# operator_mk2.net
KiCad netlist of a schematic drawn in EAGLE
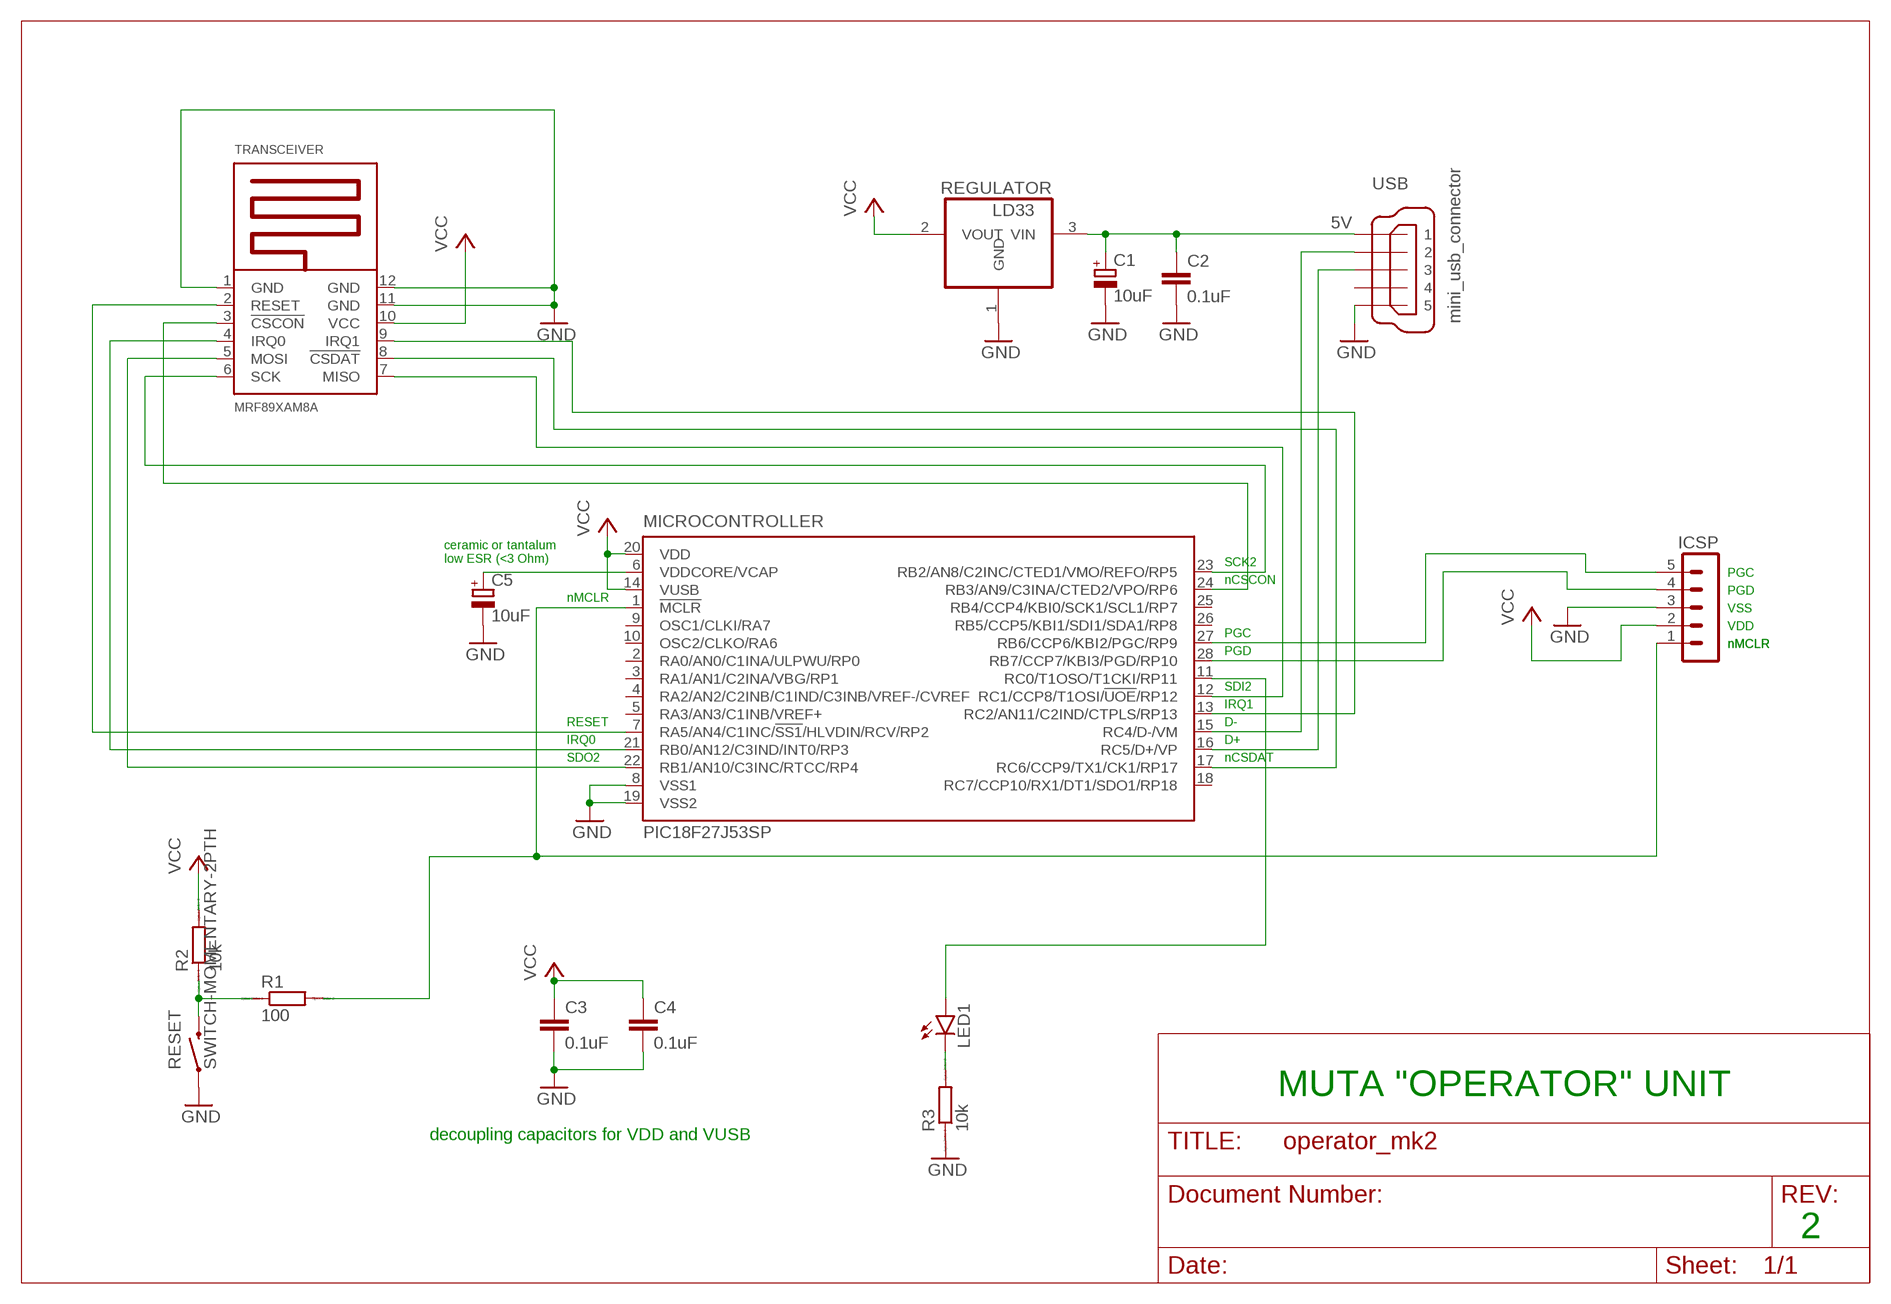
[diagram p0: schematic, sheet 1]

(export (version "E")
  (design (tool "Eeschema 10.0.6"))
  (components
    (comp (ref "C1")
      (value "10uF")
      (footprint "eagle-import:TT5D6")
      (libsource (lib "eagle-import") (part "CPOL-EUTT6D6"))
    )
    (comp (ref "C2")
      (value "0.1uF")
      (footprint "eagle-import:C050-025X075")
      (libsource (lib "eagle-import") (part "C-EU050-025X075"))
    )
    (comp (ref "C3")
      (value "0.1uF")
      (footprint "eagle-import:C050-025X075")
      (libsource (lib "eagle-import") (part "C-EU050-025X075"))
    )
    (comp (ref "C4")
      (value "0.1uF")
      (footprint "eagle-import:C050-025X075")
      (libsource (lib "eagle-import") (part "C-EU050-025X075"))
    )
    (comp (ref "C5")
      (value "10uF")
      (footprint "eagle-import:C_6032-28R")
      (libsource (lib "eagle-import") (part "CPOL-EUC/6032-28R"))
    )
    (comp (ref "ICSP")
      (value "MA05-1")
      (footprint "eagle-import:MA05-1")
      (libsource (lib "eagle-import") (part "MA05-1"))
    )
    (comp (ref "LED1")
      (value "LED5MM")
      (footprint "eagle-import:LED5MM")
      (libsource (lib "eagle-import") (part "LED5MM"))
    )
    (comp (ref "MICROCONTROLLER")
      (value "PIC18F27J53SP")
      (footprint "eagle-import:DIL28-3")
      (fields (field (name "MPN") "PIC18F27J53-I/SP"))
      (libsource (lib "eagle-import") (part "PIC18F2J53SP7"))
    )
    (comp (ref "R1")
      (value "100")
      (footprint "eagle-import:0207_10")
      (libsource (lib "eagle-import") (part "R-EU_0207_10"))
    )
    (comp (ref "R2")
      (value "10k")
      (footprint "eagle-import:0207_10")
      (libsource (lib "eagle-import") (part "R-EU_0207_10"))
    )
    (comp (ref "R3")
      (value "10k")
      (footprint "eagle-import:0207_2V")
      (libsource (lib "eagle-import") (part "R-EU_0207_2V"))
    )
    (comp (ref "REGULATOR")
      (value "LD33")
      (footprint "eagle-import:SOT223")
      (fields (field (name "MPN") "REG1117") (field (name "MPN_1") "LD33"))
      (libsource (lib "eagle-import") (part "REG1117"))
    )
    (comp (ref "RESET")
      (value "SWITCH-MOMENTARY-2PTH")
      (footprint "eagle-import:TACTILE-PTH")
      (libsource (lib "eagle-import") (part "SWITCH-MOMENTARY-2PTH"))
    )
    (comp (ref "TRANSCEIVER")
      (value "MRF89XAM8A")
      (footprint "eagle-import:MRF89XAMXA")
      (libsource (lib "eagle-import") (part "MRF89XAM8A"))
    )
    (comp (ref "USB")
      (value "mini_usb_connector")
      (footprint "eagle-import:UX60-MB-5ST")
      (libsource (lib "eagle-import") (part "MINI-USB-UX60-MB-5ST"))
    )
  )
  (nets
    (net (code "1") (name "/5V") (class "Default")
      (node (ref "C1") (pin "+") (pinfunction "+_+") (pintype "passive"))
      (node (ref "C2") (pin "1") (pinfunction "1_1") (pintype "passive"))
      (node (ref "REGULATOR") (pin "3") (pinfunction "VIN_3") (pintype "input"))
      (node (ref "USB") (pin "1") (pinfunction "1_1") (pintype "input"))
    )
    (net (code "2") (name "GND") (class "Default")
      (node (ref "C1") (pin "-") (pinfunction "-_-") (pintype "passive"))
      (node (ref "C2") (pin "2") (pinfunction "2_2") (pintype "passive"))
      (node (ref "C3") (pin "2") (pinfunction "2_2") (pintype "passive"))
      (node (ref "C4") (pin "2") (pinfunction "2_2") (pintype "passive"))
      (node (ref "C5") (pin "-") (pinfunction "-_-") (pintype "passive"))
      (node (ref "ICSP") (pin "3") (pinfunction "3_3") (pintype "passive"))
      (node (ref "MICROCONTROLLER") (pin "19") (pinfunction "VSS2_19") (pintype "input"))
      (node (ref "MICROCONTROLLER") (pin "8") (pinfunction "VSS1_8") (pintype "input"))
      (node (ref "R3") (pin "1") (pinfunction "1_1") (pintype "passive"))
      (node (ref "REGULATOR") (pin "1") (pinfunction "GND_1") (pintype "power_in"))
      (node (ref "RESET") (pin "1") (pinfunction "1_1") (pintype "passive"))
      (node (ref "TRANSCEIVER") (pin "1") (pinfunction "GND_1") (pintype "power_in"))
      (node (ref "TRANSCEIVER") (pin "11") (pinfunction "GND_11") (pintype "power_in"))
      (node (ref "TRANSCEIVER") (pin "12") (pinfunction "GND_12") (pintype "power_in"))
      (node (ref "USB") (pin "5") (pinfunction "5_5") (pintype "input"))
    )
    (net (code "3") (name "Net-(LED1-C)") (class "Default")
      (node (ref "LED1") (pin "K") (pinfunction "C_K") (pintype "passive"))
      (node (ref "R3") (pin "2") (pinfunction "2_2") (pintype "passive"))
    )
    (net (code "4") (name "Net-(MICROCONTROLLER-RA5{slash}AN4{slash}C1INC{slash}~{SS1}{slash}HLVDIN{slash}RCV{slash}RP2)") (class "Default")
      (node (ref "MICROCONTROLLER") (pin "7") (pinfunction "RA5/AN4/C1INC/~{SS1}/HLVDIN/RCV/RP2_7") (pintype "bidirectional"))
      (node (ref "TRANSCEIVER") (pin "2") (pinfunction "RESET_2") (pintype "input"))
    )
    (net (code "5") (name "Net-(MICROCONTROLLER-RB0{slash}AN12{slash}C3IND{slash}INT0{slash}RP3)") (class "Default")
      (node (ref "MICROCONTROLLER") (pin "21") (pinfunction "RB0/AN12/C3IND/INT0/RP3_21") (pintype "bidirectional"))
      (node (ref "TRANSCEIVER") (pin "4") (pinfunction "IRQ0_4") (pintype "output"))
    )
    (net (code "6") (name "Net-(MICROCONTROLLER-RB1{slash}AN10{slash}C3INC{slash}RTCC{slash}RP4)") (class "Default")
      (node (ref "MICROCONTROLLER") (pin "22") (pinfunction "RB1/AN10/C3INC/RTCC/RP4_22") (pintype "bidirectional"))
      (node (ref "TRANSCEIVER") (pin "5") (pinfunction "MOSI_5") (pintype "input"))
    )
    (net (code "7") (name "Net-(MICROCONTROLLER-RB2{slash}AN8{slash}C2INC{slash}CTED1{slash}VMO{slash}REFO{slash}RP5)") (class "Default")
      (node (ref "MICROCONTROLLER") (pin "23") (pinfunction "RB2/AN8/C2INC/CTED1/VMO/REFO/RP5_23") (pintype "bidirectional"))
      (node (ref "TRANSCEIVER") (pin "6") (pinfunction "SCK_6") (pintype "input"))
    )
    (net (code "8") (name "Net-(MICROCONTROLLER-RB3{slash}AN9{slash}C3INA{slash}CTED2{slash}VPO{slash}RP6)") (class "Default")
      (node (ref "MICROCONTROLLER") (pin "24") (pinfunction "RB3/AN9/C3INA/CTED2/VPO/RP6_24") (pintype "bidirectional"))
      (node (ref "TRANSCEIVER") (pin "3") (pinfunction "~{CSCON}_3") (pintype "input"))
    )
    (net (code "9") (name "Net-(MICROCONTROLLER-RB6{slash}CCP6{slash}KBI2{slash}PGC{slash}RP9)") (class "Default")
      (node (ref "ICSP") (pin "5") (pinfunction "5_5") (pintype "passive"))
      (node (ref "MICROCONTROLLER") (pin "27") (pinfunction "RB6/CCP6/KBI2/PGC/RP9_27") (pintype "bidirectional"))
    )
    (net (code "10") (name "Net-(MICROCONTROLLER-RB7{slash}CCP7{slash}KBI3{slash}PGD{slash}RP10)") (class "Default")
      (node (ref "ICSP") (pin "4") (pinfunction "4_4") (pintype "passive"))
      (node (ref "MICROCONTROLLER") (pin "28") (pinfunction "RB7/CCP7/KBI3/PGD/RP10_28") (pintype "bidirectional"))
    )
    (net (code "11") (name "Net-(MICROCONTROLLER-RC0{slash}T1OSO{slash}T1CKI{slash}RP11)") (class "Default")
      (node (ref "LED1") (pin "A") (pinfunction "A_A") (pintype "passive"))
      (node (ref "MICROCONTROLLER") (pin "11") (pinfunction "RC0/T1OSO/T1CKI/RP11_11") (pintype "bidirectional"))
    )
    (net (code "12") (name "Net-(MICROCONTROLLER-RC1{slash}CCP8{slash}T1OSI{slash}~{UOE}{slash}RP12)") (class "Default")
      (node (ref "MICROCONTROLLER") (pin "12") (pinfunction "RC1/CCP8/T1OSI/~{UOE}/RP12_12") (pintype "bidirectional"))
      (node (ref "TRANSCEIVER") (pin "7") (pinfunction "MISO_7") (pintype "output"))
    )
    (net (code "13") (name "Net-(MICROCONTROLLER-RC2{slash}AN11{slash}C2IND{slash}CTPLS{slash}RP13)") (class "Default")
      (node (ref "MICROCONTROLLER") (pin "13") (pinfunction "RC2/AN11/C2IND/CTPLS/RP13_13") (pintype "bidirectional"))
      (node (ref "TRANSCEIVER") (pin "9") (pinfunction "IRQ1_9") (pintype "output"))
    )
    (net (code "14") (name "Net-(MICROCONTROLLER-RC4{slash}D-{slash}VM)") (class "Default")
      (node (ref "MICROCONTROLLER") (pin "15") (pinfunction "RC4/D-/VM_15") (pintype "bidirectional"))
      (node (ref "USB") (pin "2") (pinfunction "2_2") (pintype "input"))
    )
    (net (code "15") (name "Net-(MICROCONTROLLER-RC5{slash}D+{slash}VP)") (class "Default")
      (node (ref "MICROCONTROLLER") (pin "16") (pinfunction "RC5/D+/VP_16") (pintype "bidirectional"))
      (node (ref "USB") (pin "3") (pinfunction "3_3") (pintype "input"))
    )
    (net (code "16") (name "Net-(MICROCONTROLLER-RC6{slash}CCP9{slash}TX1{slash}CK1{slash}RP17)") (class "Default")
      (node (ref "MICROCONTROLLER") (pin "17") (pinfunction "RC6/CCP9/TX1/CK1/RP17_17") (pintype "bidirectional"))
      (node (ref "TRANSCEIVER") (pin "8") (pinfunction "~{CSDAT}_8") (pintype "input"))
    )
    (net (code "17") (name "Net-(MICROCONTROLLER-VDDCORE{slash}VCAP)") (class "Default")
      (node (ref "C5") (pin "+") (pinfunction "+_+") (pintype "passive"))
      (node (ref "MICROCONTROLLER") (pin "6") (pinfunction "VDDCORE/VCAP_6") (pintype "input"))
    )
    (net (code "18") (name "Net-(MICROCONTROLLER-~{MCLR})") (class "Default")
      (node (ref "ICSP") (pin "1") (pinfunction "1_1") (pintype "passive"))
      (node (ref "MICROCONTROLLER") (pin "1") (pinfunction "~{MCLR}_1") (pintype "input"))
      (node (ref "R1") (pin "2") (pinfunction "2_2") (pintype "passive"))
    )
    (net (code "19") (name "Net-(RESET-2)") (class "Default")
      (node (ref "R1") (pin "1") (pinfunction "1_1") (pintype "passive"))
      (node (ref "R2") (pin "1") (pinfunction "1_1") (pintype "passive"))
      (node (ref "RESET") (pin "3") (pinfunction "2_3") (pintype "passive"))
    )
    (net (code "20") (name "VCC") (class "Default")
      (node (ref "C3") (pin "1") (pinfunction "1_1") (pintype "passive"))
      (node (ref "C4") (pin "1") (pinfunction "1_1") (pintype "passive"))
      (node (ref "ICSP") (pin "2") (pinfunction "2_2") (pintype "passive"))
      (node (ref "MICROCONTROLLER") (pin "14") (pinfunction "VUSB_14") (pintype "input"))
      (node (ref "MICROCONTROLLER") (pin "20") (pinfunction "VDD_20") (pintype "input"))
      (node (ref "R2") (pin "2") (pinfunction "2_2") (pintype "passive"))
      (node (ref "REGULATOR") (pin "2") (pinfunction "VOUT_2") (pintype "output"))
      (node (ref "TRANSCEIVER") (pin "10") (pinfunction "VCC_10") (pintype "power_in"))
    )
    (net (code "21") (name "unconnected-(MICROCONTROLLER-OSC1{slash}CLKI{slash}RA7-Pad9)") (class "Default")
      (node (ref "MICROCONTROLLER") (pin "9") (pinfunction "OSC1/CLKI/RA7_9") (pintype "bidirectional"))
    )
    (net (code "22") (name "unconnected-(MICROCONTROLLER-OSC2{slash}CLKO{slash}RA6-Pad10)") (class "Default")
      (node (ref "MICROCONTROLLER") (pin "10") (pinfunction "OSC2/CLKO/RA6_10") (pintype "bidirectional"))
    )
    (net (code "23") (name "unconnected-(MICROCONTROLLER-RA0{slash}AN0{slash}C1INA{slash}ULPWU{slash}RP0-Pad2)") (class "Default")
      (node (ref "MICROCONTROLLER") (pin "2") (pinfunction "RA0/AN0/C1INA/ULPWU/RP0_2") (pintype "bidirectional"))
    )
    (net (code "24") (name "unconnected-(MICROCONTROLLER-RA1{slash}AN1{slash}C2INA{slash}VBG{slash}RP1-Pad3)") (class "Default")
      (node (ref "MICROCONTROLLER") (pin "3") (pinfunction "RA1/AN1/C2INA/VBG/RP1_3") (pintype "bidirectional"))
    )
    (net (code "25") (name "unconnected-(MICROCONTROLLER-RA2{slash}AN2{slash}C2INB{slash}C1IND{slash}C3INB{slash}VREF-{slash}CVREF-Pad4)") (class "Default")
      (node (ref "MICROCONTROLLER") (pin "4") (pinfunction "RA2/AN2/C2INB/C1IND/C3INB/VREF-/CVREF_4") (pintype "bidirectional"))
    )
    (net (code "26") (name "unconnected-(MICROCONTROLLER-RA3{slash}AN3{slash}C1INB{slash}VREF+-Pad5)") (class "Default")
      (node (ref "MICROCONTROLLER") (pin "5") (pinfunction "RA3/AN3/C1INB/VREF+_5") (pintype "bidirectional"))
    )
    (net (code "27") (name "unconnected-(MICROCONTROLLER-RB4{slash}CCP4{slash}KBI0{slash}SCK1{slash}SCL1{slash}RP7-Pad25)") (class "Default")
      (node (ref "MICROCONTROLLER") (pin "25") (pinfunction "RB4/CCP4/KBI0/SCK1/SCL1/RP7_25") (pintype "bidirectional"))
    )
    (net (code "28") (name "unconnected-(MICROCONTROLLER-RB5{slash}CCP5{slash}KBI1{slash}SDI1{slash}SDA1{slash}RP8-Pad26)") (class "Default")
      (node (ref "MICROCONTROLLER") (pin "26") (pinfunction "RB5/CCP5/KBI1/SDI1/SDA1/RP8_26") (pintype "bidirectional"))
    )
    (net (code "29") (name "unconnected-(MICROCONTROLLER-RC7{slash}CCP10{slash}RX1{slash}DT1{slash}SDO1{slash}RP18-Pad18)") (class "Default")
      (node (ref "MICROCONTROLLER") (pin "18") (pinfunction "RC7/CCP10/RX1/DT1/SDO1/RP18_18") (pintype "bidirectional"))
    )
    (net (code "30") (name "unconnected-(USB-Pad4)") (class "Default")
      (node (ref "USB") (pin "4") (pinfunction "4_4") (pintype "input"))
    )
  )
)
